# remote_switch.net
KiCad netlist of a schematic drawn in EAGLE
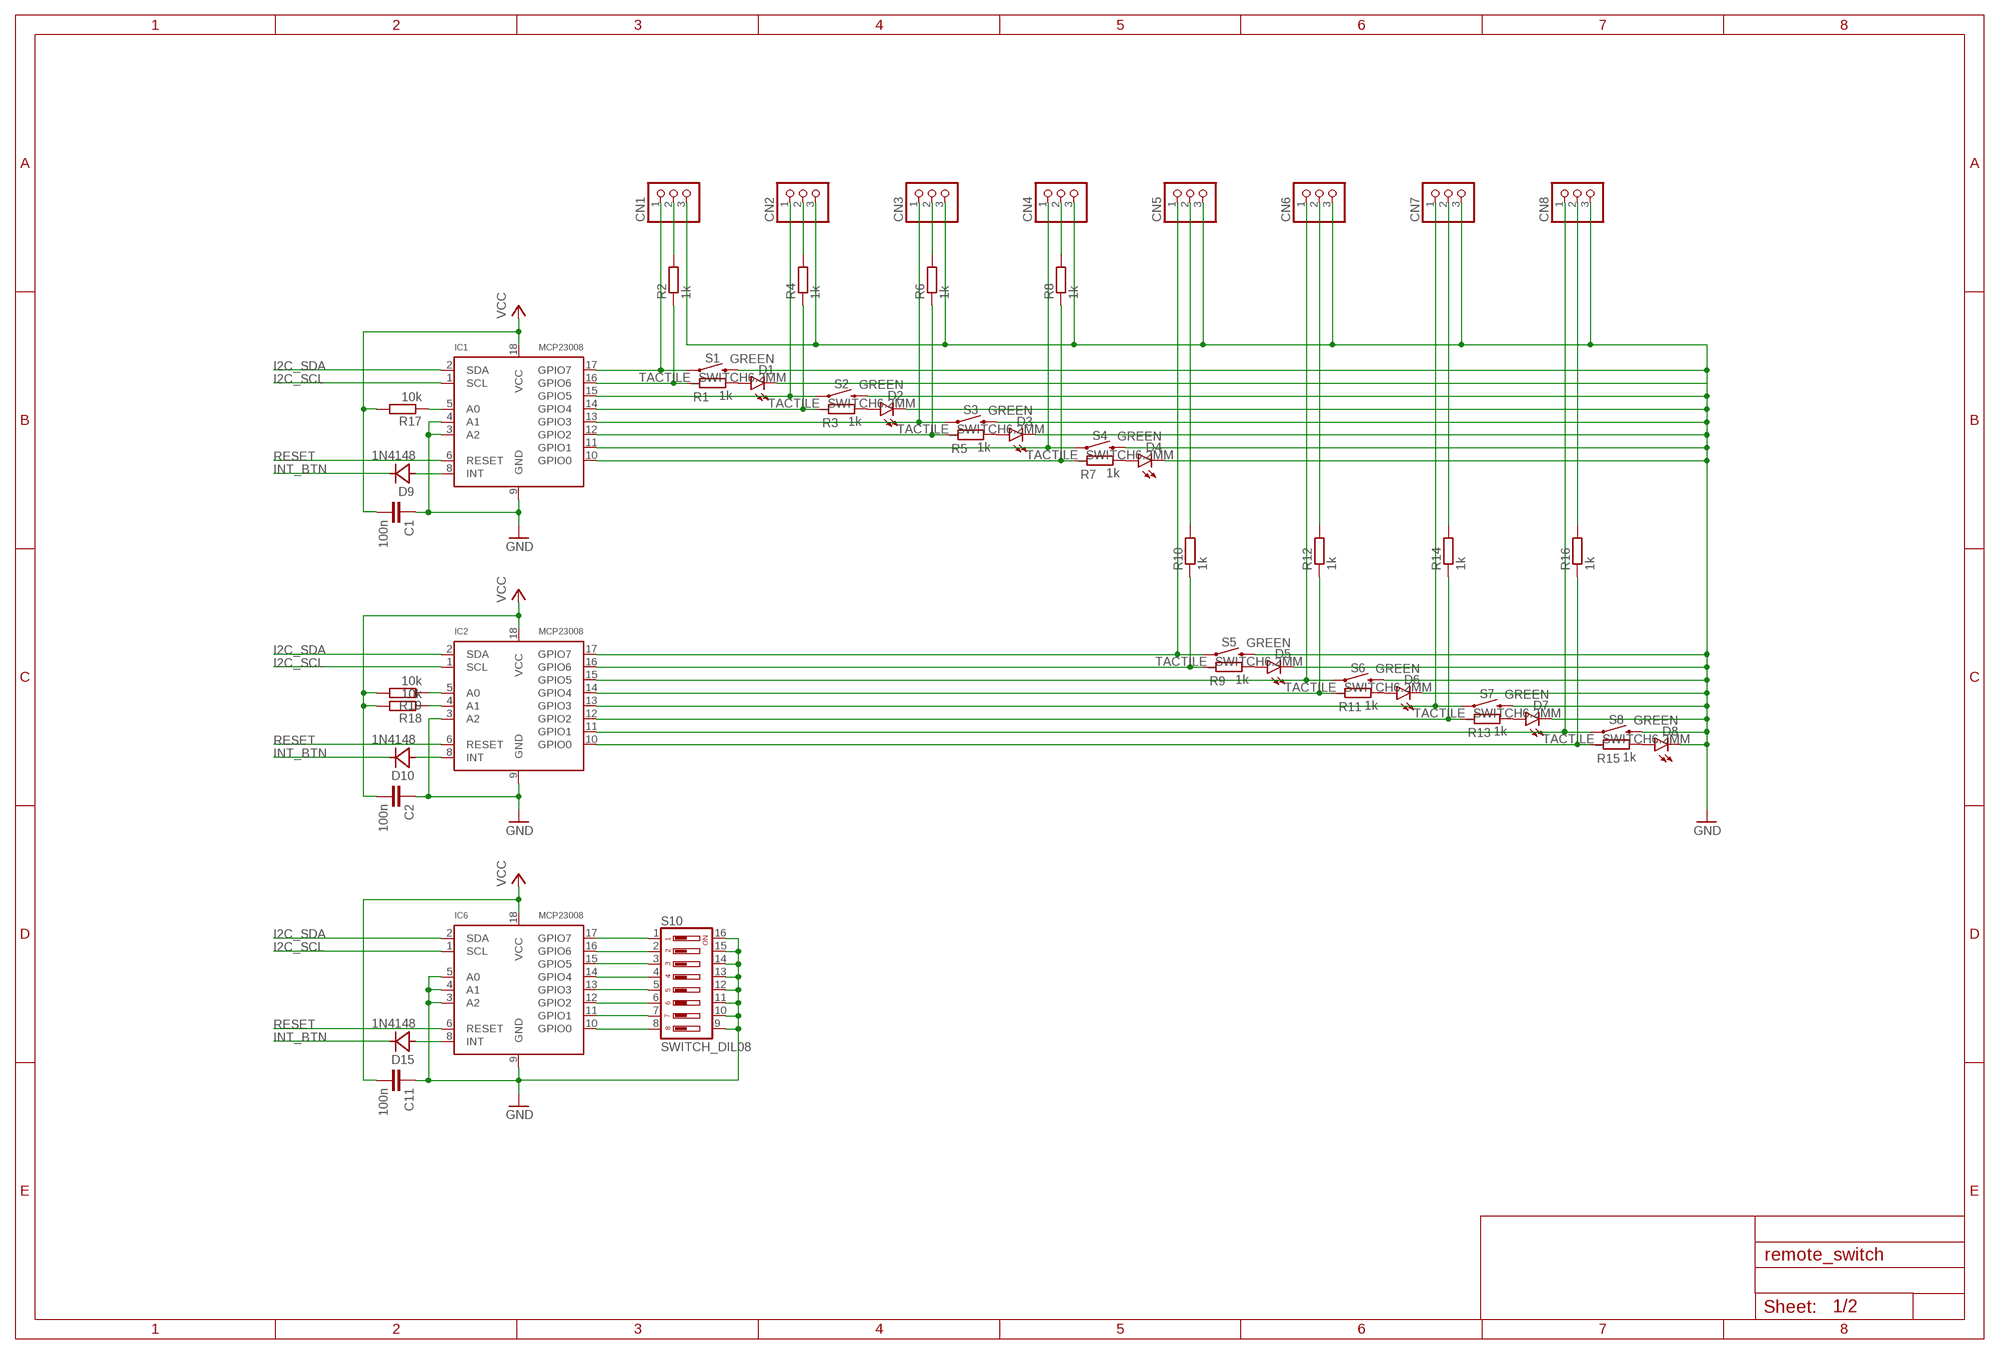
[diagram p0: schematic, sheet 1]
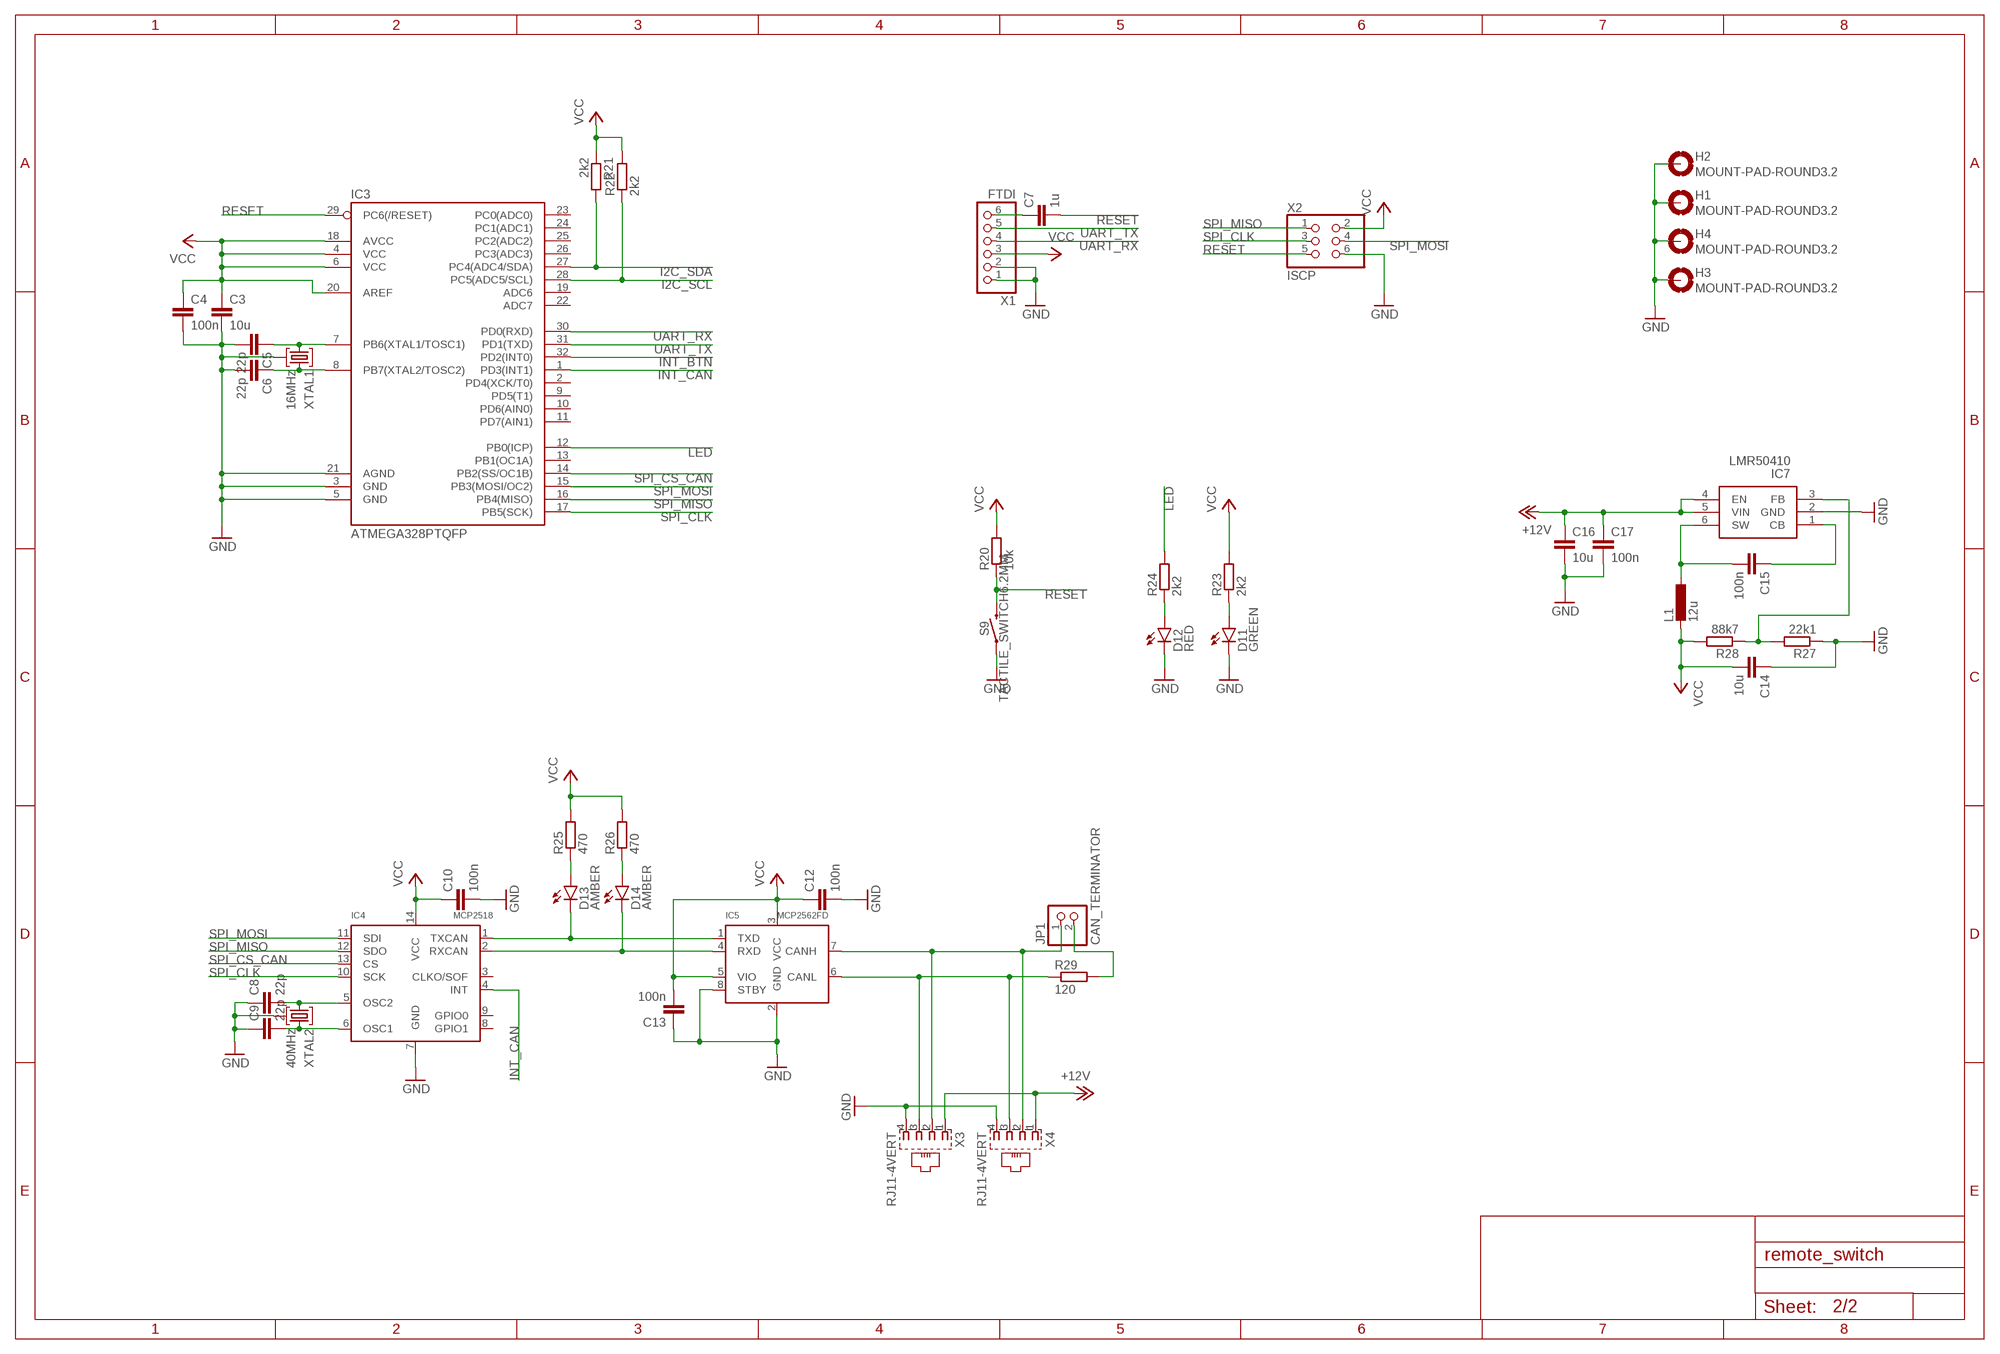
[diagram p1: schematic, sheet 2]

(export (version "E")
  (design (tool "Eeschema 10.0.6"))
  (components
    (comp (ref "C1")
      (value "100n")
      (footprint "eagle-import:C0805")
      (libsource (lib "eagle-import") (part "CAPACITOR0805"))
    )
    (comp (ref "C2")
      (value "100n")
      (footprint "eagle-import:C0805")
      (libsource (lib "eagle-import") (part "CAPACITOR0805"))
    )
    (comp (ref "C11")
      (value "100n")
      (footprint "eagle-import:C0805")
      (libsource (lib "eagle-import") (part "CAPACITOR0805"))
    )
    (comp (ref "CN1")
      (value "JST_3PIN")
      (footprint "eagle-import:JSTPH3")
      (libsource (lib "eagle-import") (part "JST_3PIN"))
    )
    (comp (ref "CN2")
      (value "JST_3PIN")
      (footprint "eagle-import:JSTPH3")
      (libsource (lib "eagle-import") (part "JST_3PIN"))
    )
    (comp (ref "CN3")
      (value "JST_3PIN")
      (footprint "eagle-import:JSTPH3")
      (libsource (lib "eagle-import") (part "JST_3PIN"))
    )
    (comp (ref "CN4")
      (value "JST_3PIN")
      (footprint "eagle-import:JSTPH3")
      (libsource (lib "eagle-import") (part "JST_3PIN"))
    )
    (comp (ref "CN5")
      (value "JST_3PIN")
      (footprint "eagle-import:JSTPH3")
      (libsource (lib "eagle-import") (part "JST_3PIN"))
    )
    (comp (ref "CN6")
      (value "JST_3PIN")
      (footprint "eagle-import:JSTPH3")
      (libsource (lib "eagle-import") (part "JST_3PIN"))
    )
    (comp (ref "CN7")
      (value "JST_3PIN")
      (footprint "eagle-import:JSTPH3")
      (libsource (lib "eagle-import") (part "JST_3PIN"))
    )
    (comp (ref "CN8")
      (value "JST_3PIN")
      (footprint "eagle-import:JSTPH3")
      (libsource (lib "eagle-import") (part "JST_3PIN"))
    )
    (comp (ref "D1")
      (value "GREEN")
      (footprint "eagle-import:CHIPLED_1206")
      (libsource (lib "eagle-import") (part "LED1206"))
    )
    (comp (ref "D2")
      (value "GREEN")
      (footprint "eagle-import:CHIPLED_1206")
      (libsource (lib "eagle-import") (part "LED1206"))
    )
    (comp (ref "D3")
      (value "GREEN")
      (footprint "eagle-import:CHIPLED_1206")
      (libsource (lib "eagle-import") (part "LED1206"))
    )
    (comp (ref "D4")
      (value "GREEN")
      (footprint "eagle-import:CHIPLED_1206")
      (libsource (lib "eagle-import") (part "LED1206"))
    )
    (comp (ref "D5")
      (value "GREEN")
      (footprint "eagle-import:CHIPLED_1206")
      (libsource (lib "eagle-import") (part "LED1206"))
    )
    (comp (ref "D6")
      (value "GREEN")
      (footprint "eagle-import:CHIPLED_1206")
      (libsource (lib "eagle-import") (part "LED1206"))
    )
    (comp (ref "D7")
      (value "GREEN")
      (footprint "eagle-import:CHIPLED_1206")
      (libsource (lib "eagle-import") (part "LED1206"))
    )
    (comp (ref "D8")
      (value "GREEN")
      (footprint "eagle-import:CHIPLED_1206")
      (libsource (lib "eagle-import") (part "LED1206"))
    )
    (comp (ref "D9")
      (value "1N4148")
      (footprint "eagle-import:SOD123")
      (libsource (lib "eagle-import") (part "DIODESOD-123"))
    )
    (comp (ref "D10")
      (value "1N4148")
      (footprint "eagle-import:SOD123")
      (libsource (lib "eagle-import") (part "DIODESOD-123"))
    )
    (comp (ref "D15")
      (value "1N4148")
      (footprint "eagle-import:SOD123")
      (libsource (lib "eagle-import") (part "DIODESOD-123"))
    )
    (comp (ref "IC1")
      (value "MCP23008")
      (footprint "eagle-import:SO18W")
      (libsource (lib "eagle-import") (part "MCP23008SO18W"))
    )
    (comp (ref "IC2")
      (value "MCP23008")
      (footprint "eagle-import:SO18W")
      (libsource (lib "eagle-import") (part "MCP23008SO18W"))
    )
    (comp (ref "IC6")
      (value "MCP23008")
      (footprint "eagle-import:SO18W")
      (libsource (lib "eagle-import") (part "MCP23008SO18W"))
    )
    (comp (ref "R1")
      (value "1k")
      (footprint "eagle-import:R0805")
      (libsource (lib "eagle-import") (part "RESISTOR0805"))
    )
    (comp (ref "R2")
      (value "1k")
      (footprint "eagle-import:R0805")
      (libsource (lib "eagle-import") (part "RESISTOR0805"))
    )
    (comp (ref "R3")
      (value "1k")
      (footprint "eagle-import:R0805")
      (libsource (lib "eagle-import") (part "RESISTOR0805"))
    )
    (comp (ref "R4")
      (value "1k")
      (footprint "eagle-import:R0805")
      (libsource (lib "eagle-import") (part "RESISTOR0805"))
    )
    (comp (ref "R5")
      (value "1k")
      (footprint "eagle-import:R0805")
      (libsource (lib "eagle-import") (part "RESISTOR0805"))
    )
    (comp (ref "R6")
      (value "1k")
      (footprint "eagle-import:R0805")
      (libsource (lib "eagle-import") (part "RESISTOR0805"))
    )
    (comp (ref "R7")
      (value "1k")
      (footprint "eagle-import:R0805")
      (libsource (lib "eagle-import") (part "RESISTOR0805"))
    )
    (comp (ref "R8")
      (value "1k")
      (footprint "eagle-import:R0805")
      (libsource (lib "eagle-import") (part "RESISTOR0805"))
    )
    (comp (ref "R9")
      (value "1k")
      (footprint "eagle-import:R0805")
      (libsource (lib "eagle-import") (part "RESISTOR0805"))
    )
    (comp (ref "R10")
      (value "1k")
      (footprint "eagle-import:R0805")
      (libsource (lib "eagle-import") (part "RESISTOR0805"))
    )
    (comp (ref "R11")
      (value "1k")
      (footprint "eagle-import:R0805")
      (libsource (lib "eagle-import") (part "RESISTOR0805"))
    )
    (comp (ref "R12")
      (value "1k")
      (footprint "eagle-import:R0805")
      (libsource (lib "eagle-import") (part "RESISTOR0805"))
    )
    (comp (ref "R13")
      (value "1k")
      (footprint "eagle-import:R0805")
      (libsource (lib "eagle-import") (part "RESISTOR0805"))
    )
    (comp (ref "R14")
      (value "1k")
      (footprint "eagle-import:R0805")
      (libsource (lib "eagle-import") (part "RESISTOR0805"))
    )
    (comp (ref "R15")
      (value "1k")
      (footprint "eagle-import:R0805")
      (libsource (lib "eagle-import") (part "RESISTOR0805"))
    )
    (comp (ref "R16")
      (value "1k")
      (footprint "eagle-import:R0805")
      (libsource (lib "eagle-import") (part "RESISTOR0805"))
    )
    (comp (ref "R17")
      (value "10k")
      (footprint "eagle-import:R0805")
      (libsource (lib "eagle-import") (part "RESISTOR0805"))
    )
    (comp (ref "R18")
      (value "10k")
      (footprint "eagle-import:R0805")
      (libsource (lib "eagle-import") (part "RESISTOR0805"))
    )
    (comp (ref "R19")
      (value "10k")
      (footprint "eagle-import:R0805")
      (libsource (lib "eagle-import") (part "RESISTOR0805"))
    )
    (comp (ref "S1")
      (value "TACTILE_SWITCH6.2MM")
      (footprint "eagle-import:TACTILE_SWITCH_SMD_6.2MM")
      (libsource (lib "eagle-import") (part "TACTILE_SWITCH6.2MM"))
    )
    (comp (ref "S2")
      (value "TACTILE_SWITCH6.2MM")
      (footprint "eagle-import:TACTILE_SWITCH_SMD_6.2MM")
      (libsource (lib "eagle-import") (part "TACTILE_SWITCH6.2MM"))
    )
    (comp (ref "S3")
      (value "TACTILE_SWITCH6.2MM")
      (footprint "eagle-import:TACTILE_SWITCH_SMD_6.2MM")
      (libsource (lib "eagle-import") (part "TACTILE_SWITCH6.2MM"))
    )
    (comp (ref "S4")
      (value "TACTILE_SWITCH6.2MM")
      (footprint "eagle-import:TACTILE_SWITCH_SMD_6.2MM")
      (libsource (lib "eagle-import") (part "TACTILE_SWITCH6.2MM"))
    )
    (comp (ref "S5")
      (value "TACTILE_SWITCH6.2MM")
      (footprint "eagle-import:TACTILE_SWITCH_SMD_6.2MM")
      (libsource (lib "eagle-import") (part "TACTILE_SWITCH6.2MM"))
    )
    (comp (ref "S6")
      (value "TACTILE_SWITCH6.2MM")
      (footprint "eagle-import:TACTILE_SWITCH_SMD_6.2MM")
      (libsource (lib "eagle-import") (part "TACTILE_SWITCH6.2MM"))
    )
    (comp (ref "S7")
      (value "TACTILE_SWITCH6.2MM")
      (footprint "eagle-import:TACTILE_SWITCH_SMD_6.2MM")
      (libsource (lib "eagle-import") (part "TACTILE_SWITCH6.2MM"))
    )
    (comp (ref "S8")
      (value "TACTILE_SWITCH6.2MM")
      (footprint "eagle-import:TACTILE_SWITCH_SMD_6.2MM")
      (libsource (lib "eagle-import") (part "TACTILE_SWITCH6.2MM"))
    )
    (comp (ref "S10")
      (value "SWITCH_DIL08")
      (footprint "eagle-import:CTS-219-08")
      (libsource (lib "eagle-import") (part "SWITCH_DIL08"))
    )
    (comp (ref "C3")
      (value "10u")
      (footprint "eagle-import:C1206")
      (libsource (lib "eagle-import") (part "CAPACITOR1206"))
    )
    (comp (ref "C4")
      (value "100n")
      (footprint "eagle-import:C0805")
      (libsource (lib "eagle-import") (part "CAPACITOR0805"))
    )
    (comp (ref "C5")
      (value "22p")
      (footprint "eagle-import:C0805")
      (libsource (lib "eagle-import") (part "CAPACITOR0805"))
    )
    (comp (ref "C6")
      (value "22p")
      (footprint "eagle-import:C0805")
      (libsource (lib "eagle-import") (part "CAPACITOR0805"))
    )
    (comp (ref "C7")
      (value "1u")
      (footprint "eagle-import:C0805")
      (libsource (lib "eagle-import") (part "CAPACITOR0805"))
    )
    (comp (ref "C8")
      (value "22p")
      (footprint "eagle-import:C0805")
      (libsource (lib "eagle-import") (part "CAPACITOR0805"))
    )
    (comp (ref "C9")
      (value "22p")
      (footprint "eagle-import:C0805")
      (libsource (lib "eagle-import") (part "CAPACITOR0805"))
    )
    (comp (ref "C10")
      (value "100n")
      (footprint "eagle-import:C0805")
      (libsource (lib "eagle-import") (part "CAPACITOR0805"))
    )
    (comp (ref "C12")
      (value "100n")
      (footprint "eagle-import:C0805")
      (libsource (lib "eagle-import") (part "CAPACITOR0805"))
    )
    (comp (ref "C13")
      (value "100n")
      (footprint "eagle-import:C0805")
      (libsource (lib "eagle-import") (part "CAPACITOR0805"))
    )
    (comp (ref "C14")
      (value "10u")
      (footprint "eagle-import:C1206")
      (libsource (lib "eagle-import") (part "CAPACITOR1206"))
    )
    (comp (ref "C15")
      (value "100n")
      (footprint "eagle-import:C0805")
      (libsource (lib "eagle-import") (part "CAPACITOR0805"))
    )
    (comp (ref "C16")
      (value "10u")
      (footprint "eagle-import:C1206")
      (libsource (lib "eagle-import") (part "CAPACITOR1206"))
    )
    (comp (ref "C17")
      (value "100n")
      (footprint "eagle-import:C0805")
      (libsource (lib "eagle-import") (part "CAPACITOR0805"))
    )
    (comp (ref "D11")
      (value "GREEN")
      (footprint "eagle-import:CHIPLED_1206")
      (libsource (lib "eagle-import") (part "LED1206"))
    )
    (comp (ref "D12")
      (value "RED")
      (footprint "eagle-import:CHIPLED_1206")
      (libsource (lib "eagle-import") (part "LED1206"))
    )
    (comp (ref "D13")
      (value "AMBER")
      (footprint "eagle-import:CHIPLED_1206")
      (libsource (lib "eagle-import") (part "LED1206"))
    )
    (comp (ref "D14")
      (value "AMBER")
      (footprint "eagle-import:CHIPLED_1206")
      (libsource (lib "eagle-import") (part "LED1206"))
    )
    (comp (ref "H1")
      (value "MOUNT-PAD-ROUND3.2")
      (footprint "eagle-import:3,2-PAD")
      (libsource (lib "eagle-import") (part "MOUNT-PAD-ROUND3.2"))
    )
    (comp (ref "H2")
      (value "MOUNT-PAD-ROUND3.2")
      (footprint "eagle-import:3,2-PAD")
      (libsource (lib "eagle-import") (part "MOUNT-PAD-ROUND3.2"))
    )
    (comp (ref "H3")
      (value "MOUNT-PAD-ROUND3.2")
      (footprint "eagle-import:3,2-PAD")
      (libsource (lib "eagle-import") (part "MOUNT-PAD-ROUND3.2"))
    )
    (comp (ref "H4")
      (value "MOUNT-PAD-ROUND3.2")
      (footprint "eagle-import:3,2-PAD")
      (libsource (lib "eagle-import") (part "MOUNT-PAD-ROUND3.2"))
    )
    (comp (ref "IC3")
      (value "ATMEGA328PTQFP")
      (footprint "eagle-import:TQFP32_0.8MM_7X7MM")
      (libsource (lib "eagle-import") (part "ATMEGA328PTQFP"))
    )
    (comp (ref "IC4")
      (value "MCP2518")
      (footprint "eagle-import:SO14")
      (libsource (lib "eagle-import") (part "MCP2518FDSO14"))
    )
    (comp (ref "IC5")
      (value "MCP2562FD")
      (footprint "eagle-import:SO08")
      (libsource (lib "eagle-import") (part "MCP2562FDSO08"))
    )
    (comp (ref "IC7")
      (value "LMR50410")
      (footprint "eagle-import:SOT23-6")
      (libsource (lib "eagle-import") (part "LMR50410"))
    )
    (comp (ref "JP1")
      (value "CAN_TERMINATOR")
      (footprint "eagle-import:1X02")
      (libsource (lib "eagle-import") (part "PINHD-1X2"))
    )
    (comp (ref "L1")
      (value "12u")
      (footprint "eagle-import:L_7.3MM")
      (libsource (lib "eagle-import") (part "INDUCTOR7.3MM"))
    )
    (comp (ref "R20")
      (value "10k")
      (footprint "eagle-import:R0805")
      (libsource (lib "eagle-import") (part "RESISTOR0805"))
    )
    (comp (ref "R21")
      (value "2k2")
      (footprint "eagle-import:R0805")
      (libsource (lib "eagle-import") (part "RESISTOR0805"))
    )
    (comp (ref "R22")
      (value "2k2")
      (footprint "eagle-import:R0805")
      (libsource (lib "eagle-import") (part "RESISTOR0805"))
    )
    (comp (ref "R23")
      (value "2k2")
      (footprint "eagle-import:R0805")
      (libsource (lib "eagle-import") (part "RESISTOR0805"))
    )
    (comp (ref "R24")
      (value "2k2")
      (footprint "eagle-import:R0805")
      (libsource (lib "eagle-import") (part "RESISTOR0805"))
    )
    (comp (ref "R25")
      (value "470")
      (footprint "eagle-import:R0805")
      (libsource (lib "eagle-import") (part "RESISTOR0805"))
    )
    (comp (ref "R26")
      (value "470")
      (footprint "eagle-import:R0805")
      (libsource (lib "eagle-import") (part "RESISTOR0805"))
    )
    (comp (ref "R27")
      (value "22k1")
      (footprint "eagle-import:R0805")
      (libsource (lib "eagle-import") (part "RESISTOR0805"))
    )
    (comp (ref "R28")
      (value "88k7")
      (footprint "eagle-import:R0805")
      (libsource (lib "eagle-import") (part "RESISTOR0805"))
    )
    (comp (ref "R29")
      (value "120")
      (footprint "eagle-import:R0805")
      (libsource (lib "eagle-import") (part "RESISTOR0805"))
    )
    (comp (ref "S9")
      (value "TACTILE_SWITCH6.2MM")
      (footprint "eagle-import:TACTILE_SWITCH_SMD_6.2MM")
      (libsource (lib "eagle-import") (part "TACTILE_SWITCH6.2MM"))
    )
    (comp (ref "X1")
      (value "FTDI")
      (footprint "eagle-import:1X06")
      (libsource (lib "eagle-import") (part "PINHD-1X6"))
    )
    (comp (ref "X2")
      (value "ISCP")
      (footprint "eagle-import:2X03")
      (libsource (lib "eagle-import") (part "PINHD-2X3"))
    )
    (comp (ref "X3")
      (value "RJ11-4VERT")
      (footprint "eagle-import:RJ11-4_VERT")
      (libsource (lib "eagle-import") (part "RJ11-4VERT"))
    )
    (comp (ref "X4")
      (value "RJ11-4VERT")
      (footprint "eagle-import:RJ11-4_VERT")
      (libsource (lib "eagle-import") (part "RJ11-4VERT"))
    )
    (comp (ref "XTAL1")
      (value "16MHz")
      (footprint "eagle-import:XTAL_5.0X3.2_4")
      (libsource (lib "eagle-import") (part "CRYSTAL_GND5X3.2"))
    )
    (comp (ref "XTAL2")
      (value "40MHz")
      (footprint "eagle-import:XTAL_5.0X3.2_4")
      (libsource (lib "eagle-import") (part "CRYSTAL_GND5X3.2"))
    )
  )
  (nets
    (net (code "1") (name "+12V") (class "Default")
      (node (ref "C16") (pin "1") (pinfunction "1_1") (pintype "passive"))
      (node (ref "C17") (pin "1") (pinfunction "1_1") (pintype "passive"))
      (node (ref "IC7") (pin "4") (pinfunction "EN_4") (pintype "bidirectional"))
      (node (ref "IC7") (pin "5") (pinfunction "VIN_5") (pintype "bidirectional"))
      (node (ref "X3") (pin "1") (pinfunction "1_1") (pintype "passive"))
      (node (ref "X4") (pin "1") (pinfunction "1_1") (pintype "passive"))
    )
    (net (code "2") (name "GND") (class "Default")
      (node (ref "C1") (pin "1") (pinfunction "1_1") (pintype "passive"))
      (node (ref "C10") (pin "2") (pinfunction "2_2") (pintype "passive"))
      (node (ref "C11") (pin "1") (pinfunction "1_1") (pintype "passive"))
      (node (ref "C12") (pin "2") (pinfunction "2_2") (pintype "passive"))
      (node (ref "C13") (pin "1") (pinfunction "1_1") (pintype "passive"))
      (node (ref "C14") (pin "1") (pinfunction "1_1") (pintype "passive"))
      (node (ref "C16") (pin "2") (pinfunction "2_2") (pintype "passive"))
      (node (ref "C17") (pin "2") (pinfunction "2_2") (pintype "passive"))
      (node (ref "C2") (pin "1") (pinfunction "1_1") (pintype "passive"))
      (node (ref "C3") (pin "2") (pinfunction "2_2") (pintype "passive"))
      (node (ref "C4") (pin "2") (pinfunction "2_2") (pintype "passive"))
      (node (ref "C5") (pin "2") (pinfunction "2_2") (pintype "passive"))
      (node (ref "C6") (pin "2") (pinfunction "2_2") (pintype "passive"))
      (node (ref "C8") (pin "1") (pinfunction "1_1") (pintype "passive"))
      (node (ref "C9") (pin "1") (pinfunction "1_1") (pintype "passive"))
      (node (ref "CN1") (pin "3") (pinfunction "3_3") (pintype "passive"))
      (node (ref "CN2") (pin "3") (pinfunction "3_3") (pintype "passive"))
      (node (ref "CN3") (pin "3") (pinfunction "3_3") (pintype "passive"))
      (node (ref "CN4") (pin "3") (pinfunction "3_3") (pintype "passive"))
      (node (ref "CN5") (pin "3") (pinfunction "3_3") (pintype "passive"))
      (node (ref "CN6") (pin "3") (pinfunction "3_3") (pintype "passive"))
      (node (ref "CN7") (pin "3") (pinfunction "3_3") (pintype "passive"))
      (node (ref "CN8") (pin "3") (pinfunction "3_3") (pintype "passive"))
      (node (ref "D1") (pin "C") (pinfunction "C_C") (pintype "passive"))
      (node (ref "D11") (pin "C") (pinfunction "C_C") (pintype "passive"))
      (node (ref "D12") (pin "C") (pinfunction "C_C") (pintype "passive"))
      (node (ref "D2") (pin "C") (pinfunction "C_C") (pintype "passive"))
      (node (ref "D3") (pin "C") (pinfunction "C_C") (pintype "passive"))
      (node (ref "D4") (pin "C") (pinfunction "C_C") (pintype "passive"))
      (node (ref "D5") (pin "C") (pinfunction "C_C") (pintype "passive"))
      (node (ref "D6") (pin "C") (pinfunction "C_C") (pintype "passive"))
      (node (ref "D7") (pin "C") (pinfunction "C_C") (pintype "passive"))
      (node (ref "D8") (pin "C") (pinfunction "C_C") (pintype "passive"))
      (node (ref "H1") (pin "B3,2") (pinfunction "MOUNT_B3,2") (pintype "passive"))
      (node (ref "H1") (pin "P$1") (pinfunction "MOUNT_P$1") (pintype "passive"))
      (node (ref "H1") (pin "P$2") (pinfunction "MOUNT_P$2") (pintype "passive"))
      (node (ref "H1") (pin "P$3") (pinfunction "MOUNT_P$3") (pintype "passive"))
      (node (ref "H1") (pin "P$4") (pinfunction "MOUNT_P$4") (pintype "passive"))
      (node (ref "H1") (pin "P$5") (pinfunction "MOUNT_P$5") (pintype "passive"))
      (node (ref "H1") (pin "P$6") (pinfunction "MOUNT_P$6") (pintype "passive"))
      (node (ref "H1") (pin "P$7") (pinfunction "MOUNT_P$7") (pintype "passive"))
      (node (ref "H1") (pin "P$8") (pinfunction "MOUNT_P$8") (pintype "passive"))
      (node (ref "H2") (pin "B3,2") (pinfunction "MOUNT_B3,2") (pintype "passive"))
      (node (ref "H2") (pin "P$1") (pinfunction "MOUNT_P$1") (pintype "passive"))
      (node (ref "H2") (pin "P$2") (pinfunction "MOUNT_P$2") (pintype "passive"))
      (node (ref "H2") (pin "P$3") (pinfunction "MOUNT_P$3") (pintype "passive"))
      (node (ref "H2") (pin "P$4") (pinfunction "MOUNT_P$4") (pintype "passive"))
      (node (ref "H2") (pin "P$5") (pinfunction "MOUNT_P$5") (pintype "passive"))
      (node (ref "H2") (pin "P$6") (pinfunction "MOUNT_P$6") (pintype "passive"))
      (node (ref "H2") (pin "P$7") (pinfunction "MOUNT_P$7") (pintype "passive"))
      (node (ref "H2") (pin "P$8") (pinfunction "MOUNT_P$8") (pintype "passive"))
      (node (ref "H3") (pin "B3,2") (pinfunction "MOUNT_B3,2") (pintype "passive"))
      (node (ref "H3") (pin "P$1") (pinfunction "MOUNT_P$1") (pintype "passive"))
      (node (ref "H3") (pin "P$2") (pinfunction "MOUNT_P$2") (pintype "passive"))
      (node (ref "H3") (pin "P$3") (pinfunction "MOUNT_P$3") (pintype "passive"))
      (node (ref "H3") (pin "P$4") (pinfunction "MOUNT_P$4") (pintype "passive"))
      (node (ref "H3") (pin "P$5") (pinfunction "MOUNT_P$5") (pintype "passive"))
      (node (ref "H3") (pin "P$6") (pinfunction "MOUNT_P$6") (pintype "passive"))
      (node (ref "H3") (pin "P$7") (pinfunction "MOUNT_P$7") (pintype "passive"))
      (node (ref "H3") (pin "P$8") (pinfunction "MOUNT_P$8") (pintype "passive"))
      (node (ref "H4") (pin "B3,2") (pinfunction "MOUNT_B3,2") (pintype "passive"))
      (node (ref "H4") (pin "P$1") (pinfunction "MOUNT_P$1") (pintype "passive"))
      (node (ref "H4") (pin "P$2") (pinfunction "MOUNT_P$2") (pintype "passive"))
      (node (ref "H4") (pin "P$3") (pinfunction "MOUNT_P$3") (pintype "passive"))
      (node (ref "H4") (pin "P$4") (pinfunction "MOUNT_P$4") (pintype "passive"))
      (node (ref "H4") (pin "P$5") (pinfunction "MOUNT_P$5") (pintype "passive"))
      (node (ref "H4") (pin "P$6") (pinfunction "MOUNT_P$6") (pintype "passive"))
      (node (ref "H4") (pin "P$7") (pinfunction "MOUNT_P$7") (pintype "passive"))
      (node (ref "H4") (pin "P$8") (pinfunction "MOUNT_P$8") (pintype "passive"))
      (node (ref "IC1") (pin "3") (pinfunction "A2_3") (pintype "bidirectional"))
      (node (ref "IC1") (pin "4") (pinfunction "A1_4") (pintype "bidirectional"))
      (node (ref "IC1") (pin "9") (pinfunction "GND_9") (pintype "bidirectional"))
      (node (ref "IC2") (pin "3") (pinfunction "A2_3") (pintype "bidirectional"))
      (node (ref "IC2") (pin "9") (pinfunction "GND_9") (pintype "bidirectional"))
      (node (ref "IC3") (pin "21") (pinfunction "AGND_21") (pintype "bidirectional"))
      (node (ref "IC3") (pin "3") (pinfunction "GND_3") (pintype "bidirectional"))
      (node (ref "IC3") (pin "5") (pinfunction "GND_5") (pintype "bidirectional"))
      (node (ref "IC4") (pin "7") (pinfunction "GND_7") (pintype "bidirectional"))
      (node (ref "IC5") (pin "2") (pinfunction "GND_2") (pintype "bidirectional"))
      (node (ref "IC5") (pin "8") (pinfunction "STBY_8") (pintype "bidirectional"))
      (node (ref "IC6") (pin "3") (pinfunction "A2_3") (pintype "bidirectional"))
      (node (ref "IC6") (pin "4") (pinfunction "A1_4") (pintype "bidirectional"))
      (node (ref "IC6") (pin "5") (pinfunction "A0_5") (pintype "bidirectional"))
      (node (ref "IC6") (pin "9") (pinfunction "GND_9") (pintype "bidirectional"))
      (node (ref "IC7") (pin "2") (pinfunction "GND_2") (pintype "bidirectional"))
      (node (ref "R27") (pin "1") (pinfunction "1_1") (pintype "passive"))
      (node (ref "S1") (pin "B1") (pinfunction "2_B1") (pintype "passive"))
      (node (ref "S1") (pin "B2") (pinfunction "2_B2") (pintype "passive"))
      (node (ref "S10") (pin "10") (pinfunction "10_10") (pintype "passive"))
      (node (ref "S10") (pin "11") (pinfunction "11_11") (pintype "passive"))
      (node (ref "S10") (pin "12") (pinfunction "12_12") (pintype "passive"))
      (node (ref "S10") (pin "13") (pinfunction "13_13") (pintype "passive"))
      (node (ref "S10") (pin "14") (pinfunction "14_14") (pintype "passive"))
      (node (ref "S10") (pin "15") (pinfunction "15_15") (pintype "passive"))
      (node (ref "S10") (pin "16") (pinfunction "16_16") (pintype "passive"))
      (node (ref "S10") (pin "9") (pinfunction "9_9") (pintype "passive"))
      (node (ref "S2") (pin "B1") (pinfunction "2_B1") (pintype "passive"))
      (node (ref "S2") (pin "B2") (pinfunction "2_B2") (pintype "passive"))
      (node (ref "S3") (pin "B1") (pinfunction "2_B1") (pintype "passive"))
      (node (ref "S3") (pin "B2") (pinfunction "2_B2") (pintype "passive"))
      (node (ref "S4") (pin "B1") (pinfunction "2_B1") (pintype "passive"))
      (node (ref "S4") (pin "B2") (pinfunction "2_B2") (pintype "passive"))
      (node (ref "S5") (pin "B1") (pinfunction "2_B1") (pintype "passive"))
      (node (ref "S5") (pin "B2") (pinfunction "2_B2") (pintype "passive"))
      (node (ref "S6") (pin "B1") (pinfunction "2_B1") (pintype "passive"))
      (node (ref "S6") (pin "B2") (pinfunction "2_B2") (pintype "passive"))
      (node (ref "S7") (pin "B1") (pinfunction "2_B1") (pintype "passive"))
      (node (ref "S7") (pin "B2") (pinfunction "2_B2") (pintype "passive"))
      (node (ref "S8") (pin "B1") (pinfunction "2_B1") (pintype "passive"))
      (node (ref "S8") (pin "B2") (pinfunction "2_B2") (pintype "passive"))
      (node (ref "S9") (pin "A1") (pinfunction "1_A1") (pintype "passive"))
      (node (ref "S9") (pin "A2") (pinfunction "1_A2") (pintype "passive"))
      (node (ref "X1") (pin "1") (pinfunction "1_1") (pintype "passive"))
      (node (ref "X1") (pin "2") (pinfunction "2_2") (pintype "passive"))
      (node (ref "X2") (pin "6") (pinfunction "6_6") (pintype "passive"))
      (node (ref "X3") (pin "4") (pinfunction "4_4") (pintype "passive"))
      (node (ref "X4") (pin "4") (pinfunction "4_4") (pintype "passive"))
      (node (ref "XTAL1") (pin "2") (pinfunction "2_2") (pintype "passive"))
      (node (ref "XTAL1") (pin "4") (pinfunction "2_4") (pintype "passive"))
      (node (ref "XTAL2") (pin "2") (pinfunction "2_2") (pintype "passive"))
      (node (ref "XTAL2") (pin "4") (pinfunction "2_4") (pintype "passive"))
    )
    (net (code "3") (name "I2C_SCL") (class "Default")
      (node (ref "IC1") (pin "1") (pinfunction "SCL_1") (pintype "bidirectional"))
      (node (ref "IC2") (pin "1") (pinfunction "SCL_1") (pintype "bidirectional"))
      (node (ref "IC3") (pin "28") (pinfunction "PC5(ADC5/SCL)_28") (pintype "bidirectional"))
      (node (ref "IC6") (pin "1") (pinfunction "SCL_1") (pintype "bidirectional"))
      (node (ref "R22") (pin "1") (pinfunction "1_1") (pintype "passive"))
    )
    (net (code "4") (name "I2C_SDA") (class "Default")
      (node (ref "IC1") (pin "2") (pinfunction "SDA_2") (pintype "bidirectional"))
      (node (ref "IC2") (pin "2") (pinfunction "SDA_2") (pintype "bidirectional"))
      (node (ref "IC3") (pin "27") (pinfunction "PC4(ADC4/SDA)_27") (pintype "bidirectional"))
      (node (ref "IC6") (pin "2") (pinfunction "SDA_2") (pintype "bidirectional"))
      (node (ref "R21") (pin "2") (pinfunction "2_2") (pintype "passive"))
    )
    (net (code "5") (name "INT_BTN") (class "Default")
      (node (ref "D10") (pin "C") (pinfunction "C_C") (pintype "passive"))
      (node (ref "D15") (pin "C") (pinfunction "C_C") (pintype "passive"))
      (node (ref "D9") (pin "C") (pinfunction "C_C") (pintype "passive"))
      (node (ref "IC3") (pin "32") (pinfunction "PD2(INT0)_32") (pintype "bidirectional"))
    )
    (net (code "6") (name "INT_CAN") (class "Default")
      (node (ref "IC3") (pin "1") (pinfunction "PD3(INT1)_1") (pintype "bidirectional"))
      (node (ref "IC4") (pin "4") (pinfunction "INT_4") (pintype "bidirectional"))
    )
    (net (code "7") (name "LED") (class "Default")
      (node (ref "IC3") (pin "12") (pinfunction "PB0(ICP)_12") (pintype "bidirectional"))
      (node (ref "R24") (pin "2") (pinfunction "2_2") (pintype "passive"))
    )
    (net (code "8") (name "Net-(C7-Pad1)") (class "Default")
      (node (ref "C7") (pin "1") (pinfunction "1_1") (pintype "passive"))
      (node (ref "X1") (pin "6") (pinfunction "6_6") (pintype "passive"))
    )
    (net (code "9") (name "Net-(CN1-Pad2)") (class "Default")
      (node (ref "CN1") (pin "2") (pinfunction "2_2") (pintype "passive"))
      (node (ref "R2") (pin "2") (pinfunction "2_2") (pintype "passive"))
    )
    (net (code "10") (name "Net-(CN2-Pad2)") (class "Default")
      (node (ref "CN2") (pin "2") (pinfunction "2_2") (pintype "passive"))
      (node (ref "R4") (pin "2") (pinfunction "2_2") (pintype "passive"))
    )
    (net (code "11") (name "Net-(CN3-Pad2)") (class "Default")
      (node (ref "CN3") (pin "2") (pinfunction "2_2") (pintype "passive"))
      (node (ref "R6") (pin "2") (pinfunction "2_2") (pintype "passive"))
    )
    (net (code "12") (name "Net-(CN4-Pad2)") (class "Default")
      (node (ref "CN4") (pin "2") (pinfunction "2_2") (pintype "passive"))
      (node (ref "R8") (pin "2") (pinfunction "2_2") (pintype "passive"))
    )
    (net (code "13") (name "Net-(CN5-Pad2)") (class "Default")
      (node (ref "CN5") (pin "2") (pinfunction "2_2") (pintype "passive"))
      (node (ref "R10") (pin "2") (pinfunction "2_2") (pintype "passive"))
    )
    (net (code "14") (name "Net-(CN6-Pad2)") (class "Default")
      (node (ref "CN6") (pin "2") (pinfunction "2_2") (pintype "passive"))
      (node (ref "R12") (pin "2") (pinfunction "2_2") (pintype "passive"))
    )
    (net (code "15") (name "Net-(CN7-Pad2)") (class "Default")
      (node (ref "CN7") (pin "2") (pinfunction "2_2") (pintype "passive"))
      (node (ref "R14") (pin "2") (pinfunction "2_2") (pintype "passive"))
    )
    (net (code "16") (name "Net-(CN8-Pad2)") (class "Default")
      (node (ref "CN8") (pin "2") (pinfunction "2_2") (pintype "passive"))
      (node (ref "R16") (pin "2") (pinfunction "2_2") (pintype "passive"))
    )
    (net (code "17") (name "Net-(D1-PadA)") (class "Default")
      (node (ref "D1") (pin "A") (pinfunction "A_A") (pintype "passive"))
      (node (ref "R1") (pin "2") (pinfunction "2_2") (pintype "passive"))
    )
    (net (code "18") (name "Net-(D2-PadA)") (class "Default")
      (node (ref "D2") (pin "A") (pinfunction "A_A") (pintype "passive"))
      (node (ref "R3") (pin "2") (pinfunction "2_2") (pintype "passive"))
    )
    (net (code "19") (name "Net-(D3-PadA)") (class "Default")
      (node (ref "D3") (pin "A") (pinfunction "A_A") (pintype "passive"))
      (node (ref "R5") (pin "2") (pinfunction "2_2") (pintype "passive"))
    )
    (net (code "20") (name "Net-(D4-PadA)") (class "Default")
      (node (ref "D4") (pin "A") (pinfunction "A_A") (pintype "passive"))
      (node (ref "R7") (pin "2") (pinfunction "2_2") (pintype "passive"))
    )
    (net (code "21") (name "Net-(D5-PadA)") (class "Default")
      (node (ref "D5") (pin "A") (pinfunction "A_A") (pintype "passive"))
      (node (ref "R9") (pin "2") (pinfunction "2_2") (pintype "passive"))
    )
    (net (code "22") (name "Net-(D6-PadA)") (class "Default")
      (node (ref "D6") (pin "A") (pinfunction "A_A") (pintype "passive"))
      (node (ref "R11") (pin "2") (pinfunction "2_2") (pintype "passive"))
    )
    (net (code "23") (name "Net-(D7-PadA)") (class "Default")
      (node (ref "D7") (pin "A") (pinfunction "A_A") (pintype "passive"))
      (node (ref "R13") (pin "2") (pinfunction "2_2") (pintype "passive"))
    )
    (net (code "24") (name "Net-(D8-PadA)") (class "Default")
      (node (ref "D8") (pin "A") (pinfunction "A_A") (pintype "passive"))
      (node (ref "R15") (pin "2") (pinfunction "2_2") (pintype "passive"))
    )
    (net (code "25") (name "Net-(D11-PadA)") (class "Default")
      (node (ref "D11") (pin "A") (pinfunction "A_A") (pintype "passive"))
      (node (ref "R23") (pin "1") (pinfunction "1_1") (pintype "passive"))
    )
    (net (code "26") (name "Net-(D12-PadA)") (class "Default")
      (node (ref "D12") (pin "A") (pinfunction "A_A") (pintype "passive"))
      (node (ref "R24") (pin "1") (pinfunction "1_1") (pintype "passive"))
    )
    (net (code "27") (name "Net-(D13-PadA)") (class "Default")
      (node (ref "D13") (pin "A") (pinfunction "A_A") (pintype "passive"))
      (node (ref "R25") (pin "1") (pinfunction "1_1") (pintype "passive"))
    )
    (net (code "28") (name "Net-(D14-PadA)") (class "Default")
      (node (ref "D14") (pin "A") (pinfunction "A_A") (pintype "passive"))
      (node (ref "R26") (pin "1") (pinfunction "1_1") (pintype "passive"))
    )
    (net (code "29") (name "Net-(IC1-A0)") (class "Default")
      (node (ref "IC1") (pin "5") (pinfunction "A0_5") (pintype "bidirectional"))
      (node (ref "R17") (pin "1") (pinfunction "1_1") (pintype "passive"))
    )
    (net (code "30") (name "Net-(IC1-GPIO0)") (class "Default")
      (node (ref "IC1") (pin "10") (pinfunction "GPIO0_10") (pintype "bidirectional"))
      (node (ref "R7") (pin "1") (pinfunction "1_1") (pintype "passive"))
      (node (ref "R8") (pin "1") (pinfunction "1_1") (pintype "passive"))
    )
    (net (code "31") (name "Net-(IC1-GPIO1)") (class "Default")
      (node (ref "CN4") (pin "1") (pinfunction "1_1") (pintype "passive"))
      (node (ref "IC1") (pin "11") (pinfunction "GPIO1_11") (pintype "bidirectional"))
      (node (ref "S4") (pin "A1") (pinfunction "1_A1") (pintype "passive"))
      (node (ref "S4") (pin "A2") (pinfunction "1_A2") (pintype "passive"))
    )
    (net (code "32") (name "Net-(IC1-GPIO2)") (class "Default")
      (node (ref "IC1") (pin "12") (pinfunction "GPIO2_12") (pintype "bidirectional"))
      (node (ref "R5") (pin "1") (pinfunction "1_1") (pintype "passive"))
      (node (ref "R6") (pin "1") (pinfunction "1_1") (pintype "passive"))
    )
    (net (code "33") (name "Net-(IC1-GPIO3)") (class "Default")
      (node (ref "CN3") (pin "1") (pinfunction "1_1") (pintype "passive"))
      (node (ref "IC1") (pin "13") (pinfunction "GPIO3_13") (pintype "bidirectional"))
      (node (ref "S3") (pin "A1") (pinfunction "1_A1") (pintype "passive"))
      (node (ref "S3") (pin "A2") (pinfunction "1_A2") (pintype "passive"))
    )
    (net (code "34") (name "Net-(IC1-GPIO4)") (class "Default")
      (node (ref "IC1") (pin "14") (pinfunction "GPIO4_14") (pintype "bidirectional"))
      (node (ref "R3") (pin "1") (pinfunction "1_1") (pintype "passive"))
      (node (ref "R4") (pin "1") (pinfunction "1_1") (pintype "passive"))
    )
    (net (code "35") (name "Net-(IC1-GPIO5)") (class "Default")
      (node (ref "CN2") (pin "1") (pinfunction "1_1") (pintype "passive"))
      (node (ref "IC1") (pin "15") (pinfunction "GPIO5_15") (pintype "bidirectional"))
      (node (ref "S2") (pin "A1") (pinfunction "1_A1") (pintype "passive"))
      (node (ref "S2") (pin "A2") (pinfunction "1_A2") (pintype "passive"))
    )
    (net (code "36") (name "Net-(IC1-GPIO6)") (class "Default")
      (node (ref "IC1") (pin "16") (pinfunction "GPIO6_16") (pintype "bidirectional"))
      (node (ref "R1") (pin "1") (pinfunction "1_1") (pintype "passive"))
      (node (ref "R2") (pin "1") (pinfunction "1_1") (pintype "passive"))
    )
    (net (code "37") (name "Net-(IC1-GPIO7)") (class "Default")
      (node (ref "CN1") (pin "1") (pinfunction "1_1") (pintype "passive"))
      (node (ref "IC1") (pin "17") (pinfunction "GPIO7_17") (pintype "bidirectional"))
      (node (ref "S1") (pin "A1") (pinfunction "1_A1") (pintype "passive"))
      (node (ref "S1") (pin "A2") (pinfunction "1_A2") (pintype "passive"))
    )
    (net (code "38") (name "Net-(IC1-INT)") (class "Default")
      (node (ref "D9") (pin "A") (pinfunction "A_A") (pintype "passive"))
      (node (ref "IC1") (pin "8") (pinfunction "INT_8") (pintype "bidirectional"))
    )
    (net (code "39") (name "Net-(IC2-A0)") (class "Default")
      (node (ref "IC2") (pin "5") (pinfunction "A0_5") (pintype "bidirectional"))
      (node (ref "R19") (pin "1") (pinfunction "1_1") (pintype "passive"))
    )
    (net (code "40") (name "Net-(IC2-A1)") (class "Default")
      (node (ref "IC2") (pin "4") (pinfunction "A1_4") (pintype "bidirectional"))
      (node (ref "R18") (pin "1") (pinfunction "1_1") (pintype "passive"))
    )
    (net (code "41") (name "Net-(IC2-GPIO0)") (class "Default")
      (node (ref "IC2") (pin "10") (pinfunction "GPIO0_10") (pintype "bidirectional"))
      (node (ref "R15") (pin "1") (pinfunction "1_1") (pintype "passive"))
      (node (ref "R16") (pin "1") (pinfunction "1_1") (pintype "passive"))
    )
    (net (code "42") (name "Net-(IC2-GPIO1)") (class "Default")
      (node (ref "CN8") (pin "1") (pinfunction "1_1") (pintype "passive"))
      (node (ref "IC2") (pin "11") (pinfunction "GPIO1_11") (pintype "bidirectional"))
      (node (ref "S8") (pin "A1") (pinfunction "1_A1") (pintype "passive"))
      (node (ref "S8") (pin "A2") (pinfunction "1_A2") (pintype "passive"))
    )
    (net (code "43") (name "Net-(IC2-GPIO2)") (class "Default")
      (node (ref "IC2") (pin "12") (pinfunction "GPIO2_12") (pintype "bidirectional"))
      (node (ref "R13") (pin "1") (pinfunction "1_1") (pintype "passive"))
      (node (ref "R14") (pin "1") (pinfunction "1_1") (pintype "passive"))
    )
    (net (code "44") (name "Net-(IC2-GPIO3)") (class "Default")
      (node (ref "CN7") (pin "1") (pinfunction "1_1") (pintype "passive"))
      (node (ref "IC2") (pin "13") (pinfunction "GPIO3_13") (pintype "bidirectional"))
      (node (ref "S7") (pin "A1") (pinfunction "1_A1") (pintype "passive"))
      (node (ref "S7") (pin "A2") (pinfunction "1_A2") (pintype "passive"))
    )
    (net (code "45") (name "Net-(IC2-GPIO4)") (class "Default")
      (node (ref "IC2") (pin "14") (pinfunction "GPIO4_14") (pintype "bidirectional"))
      (node (ref "R11") (pin "1") (pinfunction "1_1") (pintype "passive"))
      (node (ref "R12") (pin "1") (pinfunction "1_1") (pintype "passive"))
    )
    (net (code "46") (name "Net-(IC2-GPIO5)") (class "Default")
      (node (ref "CN6") (pin "1") (pinfunction "1_1") (pintype "passive"))
      (node (ref "IC2") (pin "15") (pinfunction "GPIO5_15") (pintype "bidirectional"))
      (node (ref "S6") (pin "A1") (pinfunction "1_A1") (pintype "passive"))
      (node (ref "S6") (pin "A2") (pinfunction "1_A2") (pintype "passive"))
    )
    (net (code "47") (name "Net-(IC2-GPIO6)") (class "Default")
      (node (ref "IC2") (pin "16") (pinfunction "GPIO6_16") (pintype "bidirectional"))
      (node (ref "R10") (pin "1") (pinfunction "1_1") (pintype "passive"))
      (node (ref "R9") (pin "1") (pinfunction "1_1") (pintype "passive"))
    )
    (net (code "48") (name "Net-(IC2-GPIO7)") (class "Default")
      (node (ref "CN5") (pin "1") (pinfunction "1_1") (pintype "passive"))
      (node (ref "IC2") (pin "17") (pinfunction "GPIO7_17") (pintype "bidirectional"))
      (node (ref "S5") (pin "A1") (pinfunction "1_A1") (pintype "passive"))
      (node (ref "S5") (pin "A2") (pinfunction "1_A2") (pintype "passive"))
    )
    (net (code "49") (name "Net-(IC2-INT)") (class "Default")
      (node (ref "D10") (pin "A") (pinfunction "A_A") (pintype "passive"))
      (node (ref "IC2") (pin "8") (pinfunction "INT_8") (pintype "bidirectional"))
    )
    (net (code "50") (name "Net-(IC3-PB6(XTAL1{slash}TOSC1))") (class "Default")
      (node (ref "C5") (pin "1") (pinfunction "1_1") (pintype "passive"))
      (node (ref "IC3") (pin "7") (pinfunction "PB6(XTAL1/TOSC1)_7") (pintype "bidirectional"))
      (node (ref "XTAL1") (pin "1") (pinfunction "1_1") (pintype "passive"))
    )
    (net (code "51") (name "Net-(IC3-PB7(XTAL2{slash}TOSC2))") (class "Default")
      (node (ref "C6") (pin "1") (pinfunction "1_1") (pintype "passive"))
      (node (ref "IC3") (pin "8") (pinfunction "PB7(XTAL2/TOSC2)_8") (pintype "bidirectional"))
      (node (ref "XTAL1") (pin "3") (pinfunction "3_3") (pintype "passive"))
    )
    (net (code "52") (name "Net-(IC4-OSC1)") (class "Default")
      (node (ref "C9") (pin "2") (pinfunction "2_2") (pintype "passive"))
      (node (ref "IC4") (pin "6") (pinfunction "OSC1_6") (pintype "bidirectional"))
      (node (ref "XTAL2") (pin "3") (pinfunction "3_3") (pintype "passive"))
    )
    (net (code "53") (name "Net-(IC4-OSC2)") (class "Default")
      (node (ref "C8") (pin "2") (pinfunction "2_2") (pintype "passive"))
      (node (ref "IC4") (pin "5") (pinfunction "OSC2_5") (pintype "bidirectional"))
      (node (ref "XTAL2") (pin "1") (pinfunction "1_1") (pintype "passive"))
    )
    (net (code "54") (name "Net-(IC4-RXCAN)") (class "Default")
      (node (ref "D14") (pin "C") (pinfunction "C_C") (pintype "passive"))
      (node (ref "IC4") (pin "2") (pinfunction "RXCAN_2") (pintype "bidirectional"))
      (node (ref "IC5") (pin "4") (pinfunction "RXD_4") (pintype "bidirectional"))
    )
    (net (code "55") (name "Net-(IC4-TXCAN)") (class "Default")
      (node (ref "D13") (pin "C") (pinfunction "C_C") (pintype "passive"))
      (node (ref "IC4") (pin "1") (pinfunction "TXCAN_1") (pintype "bidirectional"))
      (node (ref "IC5") (pin "1") (pinfunction "TXD_1") (pintype "bidirectional"))
    )
    (net (code "56") (name "Net-(IC5-CANH)") (class "Default")
      (node (ref "IC5") (pin "7") (pinfunction "CANH_7") (pintype "bidirectional"))
      (node (ref "JP1") (pin "1") (pinfunction "1_1") (pintype "passive"))
      (node (ref "X3") (pin "2") (pinfunction "2_2") (pintype "passive"))
      (node (ref "X4") (pin "2") (pinfunction "2_2") (pintype "passive"))
    )
    (net (code "57") (name "Net-(IC5-CANL)") (class "Default")
      (node (ref "IC5") (pin "6") (pinfunction "CANL_6") (pintype "bidirectional"))
      (node (ref "R29") (pin "1") (pinfunction "1_1") (pintype "passive"))
      (node (ref "X3") (pin "3") (pinfunction "3_3") (pintype "passive"))
      (node (ref "X4") (pin "3") (pinfunction "3_3") (pintype "passive"))
    )
    (net (code "58") (name "Net-(IC6-GPIO0)") (class "Default")
      (node (ref "IC6") (pin "10") (pinfunction "GPIO0_10") (pintype "bidirectional"))
      (node (ref "S10") (pin "8") (pinfunction "8_8") (pintype "passive"))
    )
    (net (code "59") (name "Net-(IC6-GPIO1)") (class "Default")
      (node (ref "IC6") (pin "11") (pinfunction "GPIO1_11") (pintype "bidirectional"))
      (node (ref "S10") (pin "7") (pinfunction "7_7") (pintype "passive"))
    )
    (net (code "60") (name "Net-(IC6-GPIO2)") (class "Default")
      (node (ref "IC6") (pin "12") (pinfunction "GPIO2_12") (pintype "bidirectional"))
      (node (ref "S10") (pin "6") (pinfunction "6_6") (pintype "passive"))
    )
    (net (code "61") (name "Net-(IC6-GPIO3)") (class "Default")
      (node (ref "IC6") (pin "13") (pinfunction "GPIO3_13") (pintype "bidirectional"))
      (node (ref "S10") (pin "5") (pinfunction "5_5") (pintype "passive"))
    )
    (net (code "62") (name "Net-(IC6-GPIO4)") (class "Default")
      (node (ref "IC6") (pin "14") (pinfunction "GPIO4_14") (pintype "bidirectional"))
      (node (ref "S10") (pin "4") (pinfunction "4_4") (pintype "passive"))
    )
    (net (code "63") (name "Net-(IC6-GPIO5)") (class "Default")
      (node (ref "IC6") (pin "15") (pinfunction "GPIO5_15") (pintype "bidirectional"))
      (node (ref "S10") (pin "3") (pinfunction "3_3") (pintype "passive"))
    )
    (net (code "64") (name "Net-(IC6-GPIO6)") (class "Default")
      (node (ref "IC6") (pin "16") (pinfunction "GPIO6_16") (pintype "bidirectional"))
      (node (ref "S10") (pin "2") (pinfunction "2_2") (pintype "passive"))
    )
    (net (code "65") (name "Net-(IC6-GPIO7)") (class "Default")
      (node (ref "IC6") (pin "17") (pinfunction "GPIO7_17") (pintype "bidirectional"))
      (node (ref "S10") (pin "1") (pinfunction "1_1") (pintype "passive"))
    )
    (net (code "66") (name "Net-(IC6-INT)") (class "Default")
      (node (ref "D15") (pin "A") (pinfunction "A_A") (pintype "passive"))
      (node (ref "IC6") (pin "8") (pinfunction "INT_8") (pintype "bidirectional"))
    )
    (net (code "67") (name "Net-(IC7-CB)") (class "Default")
      (node (ref "C15") (pin "1") (pinfunction "1_1") (pintype "passive"))
      (node (ref "IC7") (pin "1") (pinfunction "CB_1") (pintype "bidirectional"))
    )
    (net (code "68") (name "Net-(IC7-FB)") (class "Default")
      (node (ref "IC7") (pin "3") (pinfunction "FB_3") (pintype "bidirectional"))
      (node (ref "R27") (pin "2") (pinfunction "2_2") (pintype "passive"))
      (node (ref "R28") (pin "1") (pinfunction "1_1") (pintype "passive"))
    )
    (net (code "69") (name "Net-(IC7-SW)") (class "Default")
      (node (ref "C15") (pin "2") (pinfunction "2_2") (pintype "passive"))
      (node (ref "IC7") (pin "6") (pinfunction "SW_6") (pintype "bidirectional"))
      (node (ref "L1") (pin "1") (pinfunction "1_1") (pintype "passive"))
    )
    (net (code "70") (name "Net-(JP1-Pad2)") (class "Default")
      (node (ref "JP1") (pin "2") (pinfunction "2_2") (pintype "passive"))
      (node (ref "R29") (pin "2") (pinfunction "2_2") (pintype "passive"))
    )
    (net (code "71") (name "RESET") (class "Default")
      (node (ref "C7") (pin "2") (pinfunction "2_2") (pintype "passive"))
      (node (ref "IC1") (pin "6") (pinfunction "RESET_6") (pintype "bidirectional"))
      (node (ref "IC2") (pin "6") (pinfunction "RESET_6") (pintype "bidirectional"))
      (node (ref "IC3") (pin "29") (pinfunction "PC6(/RESET)_29") (pintype "bidirectional"))
      (node (ref "IC6") (pin "6") (pinfunction "RESET_6") (pintype "bidirectional"))
      (node (ref "R20") (pin "1") (pinfunction "1_1") (pintype "passive"))
      (node (ref "S9") (pin "B1") (pinfunction "2_B1") (pintype "passive"))
      (node (ref "S9") (pin "B2") (pinfunction "2_B2") (pintype "passive"))
      (node (ref "X2") (pin "5") (pinfunction "5_5") (pintype "passive"))
    )
    (net (code "72") (name "SPI_CLK") (class "Default")
      (node (ref "IC3") (pin "17") (pinfunction "PB5(SCK)_17") (pintype "bidirectional"))
      (node (ref "IC4") (pin "10") (pinfunction "SCK_10") (pintype "bidirectional"))
      (node (ref "X2") (pin "3") (pinfunction "3_3") (pintype "passive"))
    )
    (net (code "73") (name "SPI_CS_CAN") (class "Default")
      (node (ref "IC3") (pin "14") (pinfunction "PB2(SS/OC1B)_14") (pintype "bidirectional"))
      (node (ref "IC4") (pin "13") (pinfunction "CS_13") (pintype "bidirectional"))
    )
    (net (code "74") (name "SPI_MISO") (class "Default")
      (node (ref "IC3") (pin "16") (pinfunction "PB4(MISO)_16") (pintype "bidirectional"))
      (node (ref "IC4") (pin "12") (pinfunction "SDO_12") (pintype "bidirectional"))
      (node (ref "X2") (pin "1") (pinfunction "1_1") (pintype "passive"))
    )
    (net (code "75") (name "SPI_MOSI") (class "Default")
      (node (ref "IC3") (pin "15") (pinfunction "PB3(MOSI/OC2)_15") (pintype "bidirectional"))
      (node (ref "IC4") (pin "11") (pinfunction "SDI_11") (pintype "bidirectional"))
      (node (ref "X2") (pin "4") (pinfunction "4_4") (pintype "passive"))
    )
    (net (code "76") (name "UART_RX") (class "Default")
      (node (ref "IC3") (pin "30") (pinfunction "PD0(RXD)_30") (pintype "bidirectional"))
      (node (ref "X1") (pin "4") (pinfunction "4_4") (pintype "passive"))
    )
    (net (code "77") (name "UART_TX") (class "Default")
      (node (ref "IC3") (pin "31") (pinfunction "PD1(TXD)_31") (pintype "bidirectional"))
      (node (ref "X1") (pin "5") (pinfunction "5_5") (pintype "passive"))
    )
    (net (code "78") (name "VCC") (class "Default")
      (node (ref "C1") (pin "2") (pinfunction "2_2") (pintype "passive"))
      (node (ref "C10") (pin "1") (pinfunction "1_1") (pintype "passive"))
      (node (ref "C11") (pin "2") (pinfunction "2_2") (pintype "passive"))
      (node (ref "C12") (pin "1") (pinfunction "1_1") (pintype "passive"))
      (node (ref "C13") (pin "2") (pinfunction "2_2") (pintype "passive"))
      (node (ref "C14") (pin "2") (pinfunction "2_2") (pintype "passive"))
      (node (ref "C2") (pin "2") (pinfunction "2_2") (pintype "passive"))
      (node (ref "C3") (pin "1") (pinfunction "1_1") (pintype "passive"))
      (node (ref "C4") (pin "1") (pinfunction "1_1") (pintype "passive"))
      (node (ref "IC1") (pin "18") (pinfunction "VCC_18") (pintype "bidirectional"))
      (node (ref "IC2") (pin "18") (pinfunction "VCC_18") (pintype "bidirectional"))
      (node (ref "IC3") (pin "18") (pinfunction "AVCC_18") (pintype "bidirectional"))
      (node (ref "IC3") (pin "20") (pinfunction "AREF_20") (pintype "bidirectional"))
      (node (ref "IC3") (pin "4") (pinfunction "VCC_4") (pintype "bidirectional"))
      (node (ref "IC3") (pin "6") (pinfunction "VCC_6") (pintype "bidirectional"))
      (node (ref "IC4") (pin "14") (pinfunction "VCC_14") (pintype "bidirectional"))
      (node (ref "IC5") (pin "3") (pinfunction "VCC_3") (pintype "bidirectional"))
      (node (ref "IC5") (pin "5") (pinfunction "VIO_5") (pintype "bidirectional"))
      (node (ref "IC6") (pin "18") (pinfunction "VCC_18") (pintype "bidirectional"))
      (node (ref "L1") (pin "2") (pinfunction "2_2") (pintype "passive"))
      (node (ref "R17") (pin "2") (pinfunction "2_2") (pintype "passive"))
      (node (ref "R18") (pin "2") (pinfunction "2_2") (pintype "passive"))
      (node (ref "R19") (pin "2") (pinfunction "2_2") (pintype "passive"))
      (node (ref "R20") (pin "2") (pinfunction "2_2") (pintype "passive"))
      (node (ref "R21") (pin "1") (pinfunction "1_1") (pintype "passive"))
      (node (ref "R22") (pin "2") (pinfunction "2_2") (pintype "passive"))
      (node (ref "R23") (pin "2") (pinfunction "2_2") (pintype "passive"))
      (node (ref "R25") (pin "2") (pinfunction "2_2") (pintype "passive"))
      (node (ref "R26") (pin "2") (pinfunction "2_2") (pintype "passive"))
      (node (ref "R28") (pin "2") (pinfunction "2_2") (pintype "passive"))
      (node (ref "X1") (pin "3") (pinfunction "3_3") (pintype "passive"))
      (node (ref "X2") (pin "2") (pinfunction "2_2") (pintype "passive"))
    )
    (net (code "79") (name "unconnected-(IC3-ADC6-Pad19)") (class "Default")
      (node (ref "IC3") (pin "19") (pinfunction "ADC6_19") (pintype "bidirectional"))
    )
    (net (code "80") (name "unconnected-(IC3-ADC7-Pad22)") (class "Default")
      (node (ref "IC3") (pin "22") (pinfunction "ADC7_22") (pintype "bidirectional"))
    )
    (net (code "81") (name "unconnected-(IC3-PB1(OC1A)-Pad13)") (class "Default")
      (node (ref "IC3") (pin "13") (pinfunction "PB1(OC1A)_13") (pintype "bidirectional"))
    )
    (net (code "82") (name "unconnected-(IC3-PC0(ADC0)-Pad23)") (class "Default")
      (node (ref "IC3") (pin "23") (pinfunction "PC0(ADC0)_23") (pintype "bidirectional"))
    )
    (net (code "83") (name "unconnected-(IC3-PC1(ADC1)-Pad24)") (class "Default")
      (node (ref "IC3") (pin "24") (pinfunction "PC1(ADC1)_24") (pintype "bidirectional"))
    )
    (net (code "84") (name "unconnected-(IC3-PC2(ADC2)-Pad25)") (class "Default")
      (node (ref "IC3") (pin "25") (pinfunction "PC2(ADC2)_25") (pintype "bidirectional"))
    )
    (net (code "85") (name "unconnected-(IC3-PC3(ADC3)-Pad26)") (class "Default")
      (node (ref "IC3") (pin "26") (pinfunction "PC3(ADC3)_26") (pintype "bidirectional"))
    )
    (net (code "86") (name "unconnected-(IC3-PD4(XCK{slash}T0)-Pad2)") (class "Default")
      (node (ref "IC3") (pin "2") (pinfunction "PD4(XCK/T0)_2") (pintype "bidirectional"))
    )
    (net (code "87") (name "unconnected-(IC3-PD5(T1)-Pad9)") (class "Default")
      (node (ref "IC3") (pin "9") (pinfunction "PD5(T1)_9") (pintype "bidirectional"))
    )
    (net (code "88") (name "unconnected-(IC3-PD6(AIN0)-Pad10)") (class "Default")
      (node (ref "IC3") (pin "10") (pinfunction "PD6(AIN0)_10") (pintype "bidirectional"))
    )
    (net (code "89") (name "unconnected-(IC3-PD7(AIN1)-Pad11)") (class "Default")
      (node (ref "IC3") (pin "11") (pinfunction "PD7(AIN1)_11") (pintype "bidirectional"))
    )
    (net (code "90") (name "unconnected-(IC4-CLKO{slash}SOF-Pad3)") (class "Default")
      (node (ref "IC4") (pin "3") (pinfunction "CLKO/SOF_3") (pintype "bidirectional"))
    )
    (net (code "91") (name "unconnected-(IC4-GPIO0-Pad9)") (class "Default")
      (node (ref "IC4") (pin "9") (pinfunction "GPIO0_9") (pintype "bidirectional"))
    )
    (net (code "92") (name "unconnected-(IC4-GPIO1-Pad8)") (class "Default")
      (node (ref "IC4") (pin "8") (pinfunction "GPIO1_8") (pintype "bidirectional"))
    )
  )
)
